# alimentacion.net
KiCad netlist of a schematic drawn in Altium Designer
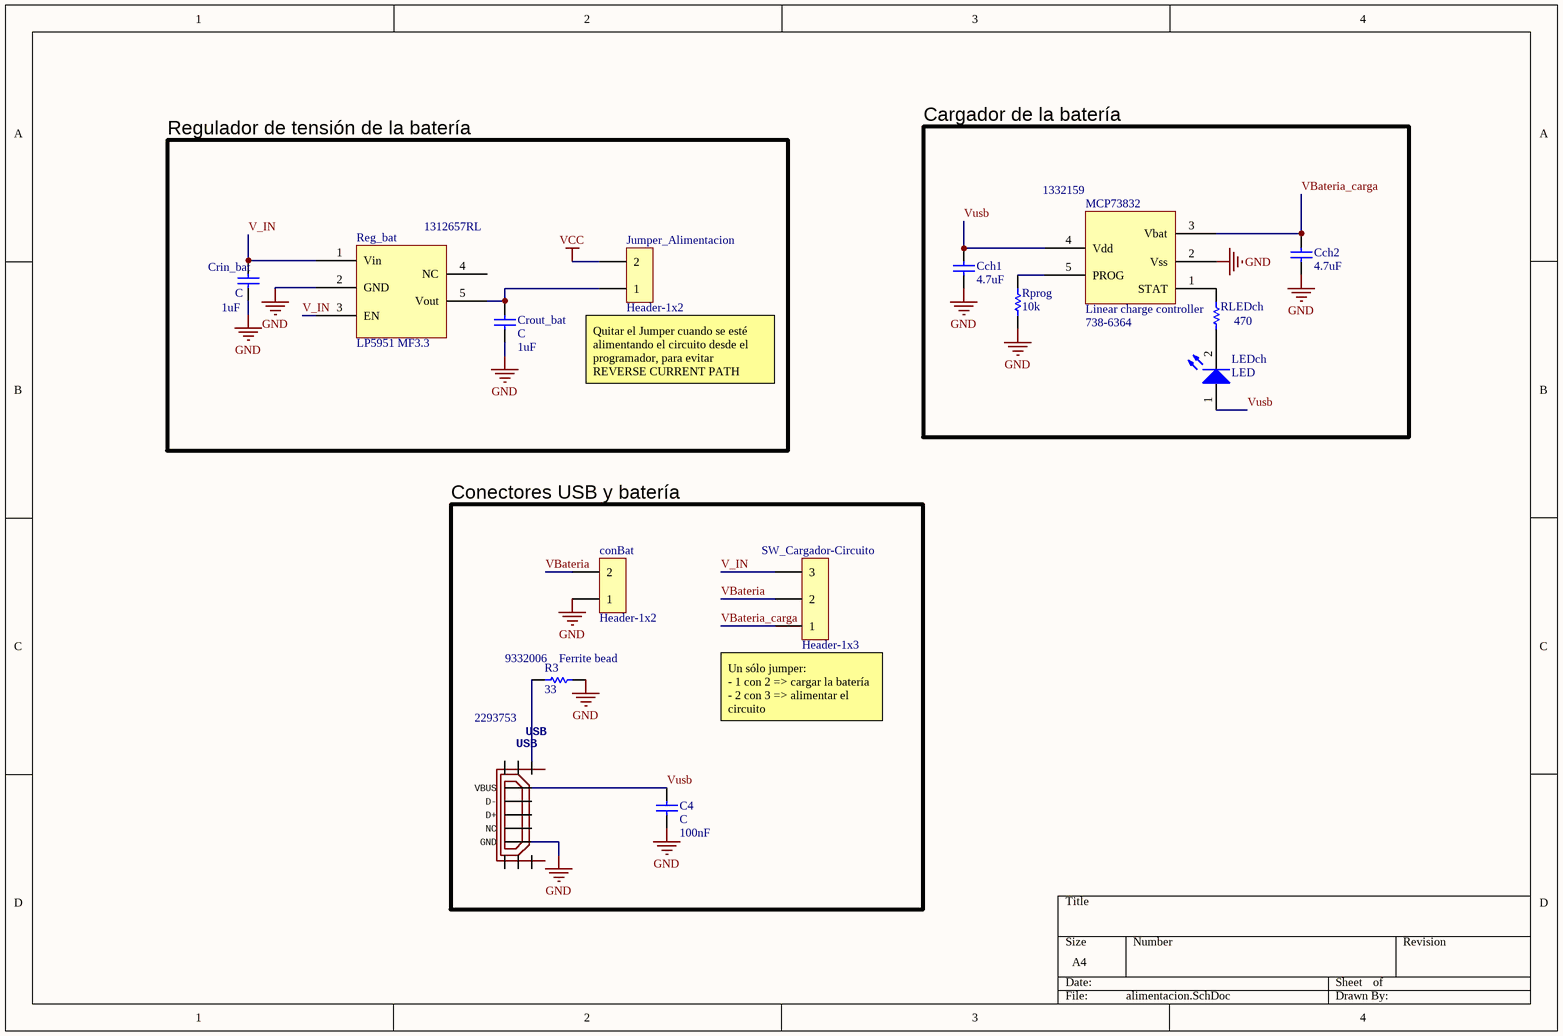
[diagram p0: alimentacion.SchDoc]

(export (version "E")
  (design (tool "Eeschema 10.0.6"))
  (components
    (comp (ref "C4")
      (value "C")
      (footprint "0805 CAP")
      (description "Capacitor")
      (fields
        (field (name "MANUFACTURER") "Generic Components")
        (field (name "ALTIUM_VALUE") "100nF")
        (field (name "PUBLISHER") "Altium Hobart Technology Centre")
      )
      (libsource (lib "LSI") (part "C"))
    )
    (comp (ref "Cch1")
      (value "4.7uF")
      (footprint "0805")
      (description "Capacitor")
      (fields
        (field (name "MANUFACTURER") "Generic Components")
        (field (name "Comment") "C")
        (field (name "PUBLISHER") "Altium Hobart Technology Centre")
      )
      (libsource (lib "LSI") (part "C"))
    )
    (comp (ref "Cch2")
      (value "4.7uF")
      (footprint "0805")
      (description "Capacitor")
      (fields
        (field (name "MANUFACTURER") "Generic Components")
        (field (name "Comment") "C")
        (field (name "PUBLISHER") "Altium Hobart Technology Centre")
      )
      (libsource (lib "LSI") (part "C"))
    )
    (comp (ref "conBat")
      (value "Header-1x2")
      (footprint "HEADER-1x2")
      (libsource (lib "B105lib") (part "Header-1x2"))
    )
    (comp (ref "Crin_bat")
      (value "C")
      (footprint "0805")
      (description "Capacitor")
      (fields
        (field (name "MANUFACTURER") "Generic Components")
        (field (name "ALTIUM_VALUE") "1uF")
        (field (name "PUBLISHER") "Altium Hobart Technology Centre")
      )
      (libsource (lib "LSI") (part "C"))
    )
    (comp (ref "Crout_bat")
      (value "C")
      (footprint "0805")
      (description "Capacitor")
      (fields
        (field (name "MANUFACTURER") "Generic Components")
        (field (name "ALTIUM_VALUE") "1uF")
        (field (name "PUBLISHER") "Altium Hobart Technology Centre")
      )
      (libsource (lib "LSI") (part "C"))
    )
    (comp (ref "Jumper_Alimentacion")
      (value "Header-1x2")
      (footprint "HEADER-1x2")
      (libsource (lib "B105lib") (part "Header-1x2"))
    )
    (comp (ref "LEDch") (value "LED") (footprint "0603 LED-RED") (libsource (lib "B105lib") (part "LED")))
    (comp (ref "MCP73832")
      (value "Linear charge controller")
      (footprint "SOT-23-5")
      (description "Linear charge controller SOT 235")
      (fields
        (field (name "SUPPLIER PART NUMBER 1") "738-6364")
        (field (name "SUPPLIER PART NUMBER 2") "1332159")
      )
      (libsource (lib "B105lib") (part "MCP73832"))
    )
    (comp (ref "R3")
      (value "Ferrite bead")
      (footprint "0805")
      (description "Resistor")
      (fields
        (field (name "MANUFACTURER") "Generic Components")
        (field (name "ALTIUM_VALUE") "33")
        (field (name "SUPPLIER PART NUMBER 1") "9332006")
        (field (name "PUBLISHER") "Altium Hobart Technology Centre")
      )
      (libsource (lib "LSI") (part "R"))
    )
    (comp (ref "Reg_bat")
      (value "LP5951 MF3.3")
      (footprint "SOT-23-5")
      (description "TI Lineal Regulator SOT 235")
      (fields (field (name "SUPPLIER PART NUMBER 1") "1312657RL"))
      (libsource (lib "sensores_quitanieves") (part "LP5951"))
    )
    (comp (ref "RLEDch")
      (value "470")
      (footprint "0805")
      (description "Resistor")
      (fields (field (name "Comment") "Res1") (field (name "PUBLISHER") "Altium Limited"))
      (libsource (lib "Miscellaneous Devices") (part "Res1"))
    )
    (comp (ref "Rprog")
      (value "10k")
      (footprint "0805")
      (description "Resistor")
      (fields (field (name "Comment") "Res1") (field (name "PUBLISHER") "Altium Limited"))
      (libsource (lib "Miscellaneous Devices") (part "Res1"))
    )
    (comp (ref "SW_Cargador-Circuito")
      (value "Header-1x3")
      (footprint "Header-1x3-Jumper")
      (libsource (lib "B105lib") (part "Header-1x3"))
    )
    (comp (ref "USB")
      (value "USB")
      (footprint "HIROSE-ZX62R-B-5P")
      (fields (field (name "SUPPLIER PART NUMBER 1") "2293753"))
      (libsource (lib "LSI") (part "USB_MICRO_FLIPPED"))
    )
  )
  (nets
    (net (code "1") (name "/VBateria") (class "Default")
      (node (ref "SW_Cargador-Circuito") (pin "2") (pinfunction "2_2") (pintype "passive"))
      (node (ref "conBat") (pin "2") (pinfunction "2_2") (pintype "passive"))
    )
    (net (code "2") (name "/VBateria_carga") (class "Default")
      (node (ref "Cch2") (pin "2") (pinfunction "2_2") (pintype "passive"))
      (node (ref "MCP73832") (pin "3") (pinfunction "Vbat_3") (pintype "passive"))
      (node (ref "SW_Cargador-Circuito") (pin "1") (pinfunction "1_1") (pintype "passive"))
    )
    (net (code "3") (name "/V_IN") (class "Default")
      (node (ref "Crin_bat") (pin "2") (pinfunction "2_2") (pintype "passive"))
      (node (ref "Reg_bat") (pin "1") (pinfunction "Vin_1") (pintype "passive"))
      (node (ref "Reg_bat") (pin "3") (pinfunction "EN_3") (pintype "passive"))
      (node (ref "SW_Cargador-Circuito") (pin "3") (pinfunction "3_3") (pintype "passive"))
    )
    (net (code "4") (name "/Vusb") (class "Default")
      (node (ref "C4") (pin "2") (pinfunction "2_2") (pintype "passive"))
      (node (ref "Cch1") (pin "2") (pinfunction "2_2") (pintype "passive"))
      (node (ref "LEDch") (pin "1") (pinfunction "A_1") (pintype "passive"))
      (node (ref "MCP73832") (pin "4") (pinfunction "Vdd_4") (pintype "passive"))
      (node (ref "USB") (pin "VBUS") (pinfunction "VBUS_VBUS") (pintype "passive"))
    )
    (net (code "5") (name "GND") (class "Default")
      (node (ref "C4") (pin "1") (pinfunction "1_1") (pintype "passive"))
      (node (ref "Cch1") (pin "1") (pinfunction "1_1") (pintype "passive"))
      (node (ref "Cch2") (pin "1") (pinfunction "1_1") (pintype "passive"))
      (node (ref "Crin_bat") (pin "1") (pinfunction "1_1") (pintype "passive"))
      (node (ref "Crout_bat") (pin "1") (pinfunction "1_1") (pintype "passive"))
      (node (ref "MCP73832") (pin "2") (pinfunction "Vss_2") (pintype "passive"))
      (node (ref "R3") (pin "1") (pinfunction "1_1") (pintype "passive"))
      (node (ref "Reg_bat") (pin "2") (pinfunction "GND_2") (pintype "passive"))
      (node (ref "Rprog") (pin "2") (pinfunction "2_2") (pintype "passive"))
      (node (ref "USB") (pin "GND") (pinfunction "GND_GND") (pintype "passive"))
      (node (ref "conBat") (pin "1") (pinfunction "1_1") (pintype "passive"))
    )
    (net (code "6") (name "Net-(LEDch-C)") (class "Default")
      (node (ref "LEDch") (pin "2") (pinfunction "C_2") (pintype "passive"))
      (node (ref "RLEDch") (pin "1") (pinfunction "1_1") (pintype "passive"))
    )
    (net (code "7") (name "Net-(MCP73832-PROG)") (class "Default")
      (node (ref "MCP73832") (pin "5") (pinfunction "PROG_5") (pintype "passive"))
      (node (ref "Rprog") (pin "1") (pinfunction "1_1") (pintype "passive"))
    )
    (net (code "8") (name "Net-(MCP73832-STAT)") (class "Default")
      (node (ref "MCP73832") (pin "1") (pinfunction "STAT_1") (pintype "passive"))
      (node (ref "RLEDch") (pin "2") (pinfunction "2_2") (pintype "passive"))
    )
    (net (code "9") (name "Net-(R3-Pad2)") (class "Default")
      (node (ref "R3") (pin "2") (pinfunction "2_2") (pintype "passive"))
      (node (ref "USB") (pin "SHIELD4") (pinfunction "SHIELD4_SHIELD4") (pintype "passive"))
    )
    (net (code "10") (name "Net-(Reg_bat-Vout)") (class "Default")
      (node (ref "Crout_bat") (pin "2") (pinfunction "2_2") (pintype "passive"))
      (node (ref "Jumper_Alimentacion") (pin "1") (pinfunction "1_1") (pintype "passive"))
      (node (ref "Reg_bat") (pin "5") (pinfunction "Vout_5") (pintype "passive"))
    )
    (net (code "11") (name "VCC") (class "Default")
      (node (ref "Jumper_Alimentacion") (pin "2") (pinfunction "2_2") (pintype "passive"))
    )
    (net (code "12") (name "unconnected-(Reg_bat-NC-Pad4)") (class "Default")
      (node (ref "Reg_bat") (pin "4") (pinfunction "NC_4") (pintype "passive"))
    )
    (net (code "13") (name "unconnected-(USB-PadD+)") (class "Default")
      (node (ref "USB") (pin "D+") (pinfunction "D+_D+") (pintype "passive"))
    )
    (net (code "14") (name "unconnected-(USB-PadD-)") (class "Default")
      (node (ref "USB") (pin "D-") (pinfunction "D-_D-") (pintype "passive"))
    )
    (net (code "15") (name "unconnected-(USB-PadNC)") (class "Default")
      (node (ref "USB") (pin "NC") (pinfunction "NC_NC") (pintype "passive"))
    )
    (net (code "16") (name "unconnected-(USB-PadSHIELD1)") (class "Default")
      (node (ref "USB") (pin "SHIELD1") (pinfunction "SHIELD1_SHIELD1") (pintype "passive"))
    )
    (net (code "17") (name "unconnected-(USB-PadSHIELD2)") (class "Default")
      (node (ref "USB") (pin "SHIELD2") (pinfunction "SHIELD2_SHIELD2") (pintype "passive"))
    )
    (net (code "18") (name "unconnected-(USB-PadSHIELD3)") (class "Default")
      (node (ref "USB") (pin "SHIELD3") (pinfunction "SHIELD3_SHIELD3") (pintype "passive"))
    )
    (net (code "19") (name "unconnected-(USB-PadSHIELD5)") (class "Default")
      (node (ref "USB") (pin "SHIELD5") (pinfunction "SHIELD5_SHIELD5") (pintype "passive"))
    )
    (net (code "20") (name "unconnected-(USB-PadSHIELD6)") (class "Default")
      (node (ref "USB") (pin "SHIELD6") (pinfunction "SHIELD6_SHIELD6") (pintype "passive"))
    )
  )
)
